# fCPU.net
KiCad netlist of a schematic drawn in EAGLE
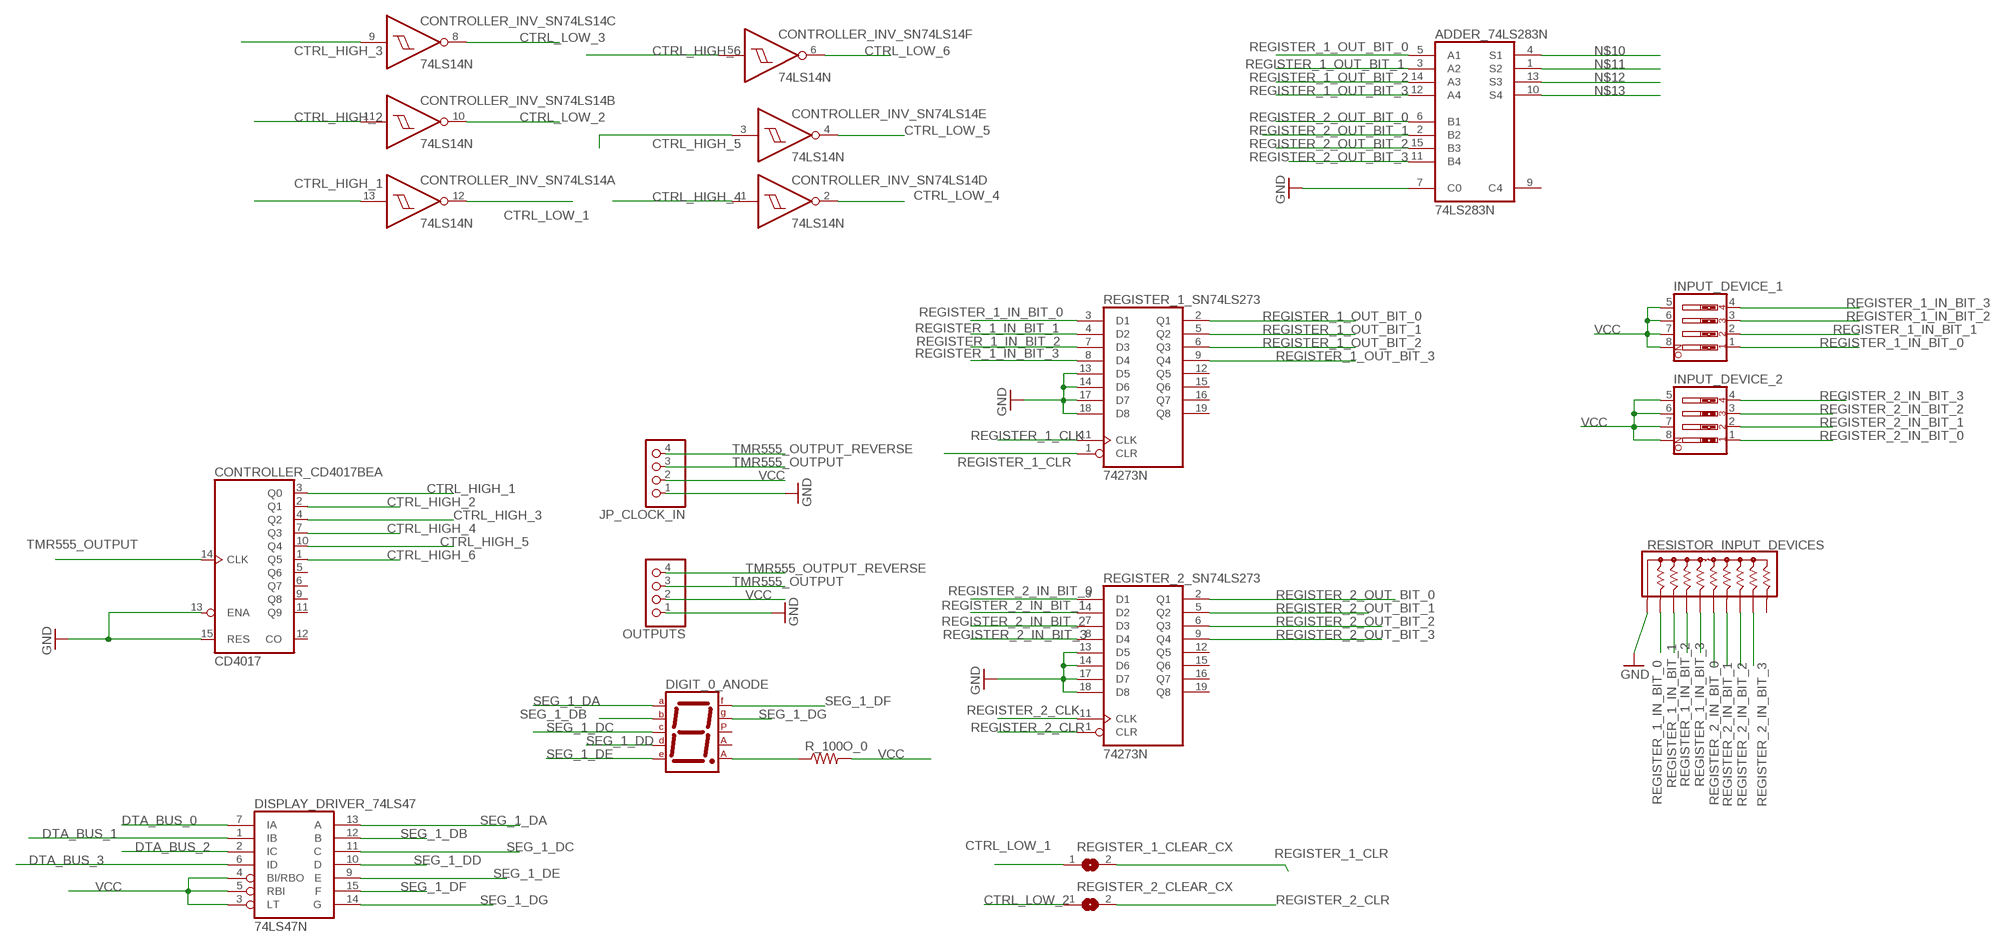
[diagram p0: schematic, sheet 1]

(export (version "E")
  (design (tool "Eeschema 10.0.6"))
  (components
    (comp (ref "ADDER_74LS283N")
      (value "74LS283N")
      (footprint "eagle-import:DIL16")
      (libsource (lib "eagle-import") (part "74283NLS"))
    )
    (comp (ref "CONTROLLER_CD4017BE")
      (value "CD4017")
      (footprint "eagle-import:DIL16")
      (libsource (lib "eagle-import") (part "CD4017"))
    )
    (comp (ref "CONTROLLER_INV_SN74LS14")
      (value "74LS14N")
      (footprint "eagle-import:DIL14")
      (libsource (lib "eagle-import") (part "7414NLS"))
    )
    (comp (ref "DIGIT_0_ANODE")
      (value "7SEG-CA")
      (footprint "eagle-import:7SEG-13")
      (libsource (lib "eagle-import") (part "7SEG-CA"))
    )
    (comp (ref "DISPLAY_DRIVER_74LS47")
      (value "74LS47N")
      (footprint "eagle-import:DIL16")
      (libsource (lib "eagle-import") (part "7447NLS"))
    )
    (comp (ref "INPUT_DEVICE_1")
      (value "SW_DIP-4")
      (footprint "eagle-import:EDG-04")
      (libsource (lib "eagle-import") (part "SW_DIP-4"))
    )
    (comp (ref "INPUT_DEVICE_2")
      (value "SW_DIP-4")
      (footprint "eagle-import:EDG-04")
      (libsource (lib "eagle-import") (part "SW_DIP-4"))
    )
    (comp (ref "JP_CLOCK_IN")
      (value "PINHD-1X4")
      (footprint "eagle-import:1X04")
      (libsource (lib "eagle-import") (part "PINHD-1X4"))
    )
    (comp (ref "OUTPUTS")
      (value "PINHD-1X4")
      (footprint "eagle-import:1X04")
      (libsource (lib "eagle-import") (part "PINHD-1X4"))
    )
    (comp (ref "REGISTER_1_CLEAR_CX")
      (value "SOLDERJUMPERREFLOW")
      (footprint "eagle-import:SOLDERJUMPER_REFLOW")
      (libsource (lib "eagle-import") (part "SOLDERJUMPERREFLOW"))
    )
    (comp (ref "REGISTER_1_SN74LS273")
      (value "74273N")
      (footprint "eagle-import:DIL20")
      (libsource (lib "eagle-import") (part "74273N"))
    )
    (comp (ref "REGISTER_2_CLEAR_CX")
      (value "SOLDERJUMPERREFLOW")
      (footprint "eagle-import:SOLDERJUMPER_REFLOW")
      (libsource (lib "eagle-import") (part "SOLDERJUMPERREFLOW"))
    )
    (comp (ref "REGISTER_2_SN74LS273")
      (value "74273N")
      (footprint "eagle-import:DIL20")
      (libsource (lib "eagle-import") (part "74273N"))
    )
    (comp (ref "RESISTOR_INPUT_DEVICES")
      (value "4610X")
      (footprint "eagle-import:SIP10")
      (libsource (lib "eagle-import") (part "4610X"))
    )
    (comp (ref "R_100O_0")
      (value "R-US_R1206")
      (footprint "eagle-import:R1206")
      (libsource (lib "eagle-import") (part "R-US_R1206"))
    )
  )
  (nets
    (net (code "1") (name "/CTRL_HIGH_1") (class "Default")
      (node (ref "CONTROLLER_CD4017BE") (pin "3") (pinfunction "Q0_3") (pintype "output"))
      (node (ref "CONTROLLER_INV_SN74LS14") (pin "13") (pinfunction "I_13") (pintype "input"))
    )
    (net (code "2") (name "/CTRL_HIGH_2") (class "Default")
      (node (ref "CONTROLLER_CD4017BE") (pin "2") (pinfunction "Q1_2") (pintype "output"))
      (node (ref "CONTROLLER_INV_SN74LS14") (pin "11") (pinfunction "I_11") (pintype "input"))
    )
    (net (code "3") (name "/CTRL_HIGH_3") (class "Default")
      (node (ref "CONTROLLER_CD4017BE") (pin "4") (pinfunction "Q2_4") (pintype "output"))
      (node (ref "CONTROLLER_INV_SN74LS14") (pin "9") (pinfunction "I_9") (pintype "input"))
    )
    (net (code "4") (name "/CTRL_HIGH_4") (class "Default")
      (node (ref "CONTROLLER_CD4017BE") (pin "7") (pinfunction "Q3_7") (pintype "output"))
      (node (ref "CONTROLLER_INV_SN74LS14") (pin "1") (pinfunction "I_1") (pintype "input"))
    )
    (net (code "5") (name "/CTRL_HIGH_5") (class "Default")
      (node (ref "CONTROLLER_CD4017BE") (pin "10") (pinfunction "Q4_10") (pintype "output"))
      (node (ref "CONTROLLER_INV_SN74LS14") (pin "3") (pinfunction "I_3") (pintype "input"))
    )
    (net (code "6") (name "/CTRL_HIGH_6") (class "Default")
      (node (ref "CONTROLLER_CD4017BE") (pin "1") (pinfunction "Q5_1") (pintype "output"))
      (node (ref "CONTROLLER_INV_SN74LS14") (pin "5") (pinfunction "I_5") (pintype "input"))
    )
    (net (code "7") (name "/CTRL_LOW_1") (class "Default")
      (node (ref "CONTROLLER_INV_SN74LS14") (pin "12") (pinfunction "O_12") (pintype "output"))
      (node (ref "REGISTER_1_CLEAR_CX") (pin "1") (pinfunction "1_1") (pintype "passive"))
    )
    (net (code "8") (name "/CTRL_LOW_2") (class "Default")
      (node (ref "CONTROLLER_INV_SN74LS14") (pin "10") (pinfunction "O_10") (pintype "output"))
      (node (ref "REGISTER_2_CLEAR_CX") (pin "1") (pinfunction "1_1") (pintype "passive"))
    )
    (net (code "9") (name "/CTRL_LOW_3") (class "Default")
      (node (ref "CONTROLLER_INV_SN74LS14") (pin "8") (pinfunction "O_8") (pintype "output"))
    )
    (net (code "10") (name "/CTRL_LOW_4") (class "Default")
      (node (ref "CONTROLLER_INV_SN74LS14") (pin "2") (pinfunction "O_2") (pintype "output"))
    )
    (net (code "11") (name "/CTRL_LOW_5") (class "Default")
      (node (ref "CONTROLLER_INV_SN74LS14") (pin "4") (pinfunction "O_4") (pintype "output"))
    )
    (net (code "12") (name "/CTRL_LOW_6") (class "Default")
      (node (ref "CONTROLLER_INV_SN74LS14") (pin "6") (pinfunction "O_6") (pintype "output"))
    )
    (net (code "13") (name "/DTA_BUS_0") (class "Default")
      (node (ref "DISPLAY_DRIVER_74LS47") (pin "7") (pinfunction "IA_7") (pintype "input"))
    )
    (net (code "14") (name "/DTA_BUS_1") (class "Default")
      (node (ref "DISPLAY_DRIVER_74LS47") (pin "1") (pinfunction "IB_1") (pintype "input"))
    )
    (net (code "15") (name "/DTA_BUS_2") (class "Default")
      (node (ref "DISPLAY_DRIVER_74LS47") (pin "2") (pinfunction "IC_2") (pintype "input"))
    )
    (net (code "16") (name "/DTA_BUS_3") (class "Default")
      (node (ref "DISPLAY_DRIVER_74LS47") (pin "6") (pinfunction "ID_6") (pintype "input"))
    )
    (net (code "17") (name "/N$10") (class "Default")
      (node (ref "ADDER_74LS283N") (pin "4") (pinfunction "S1_4") (pintype "output"))
    )
    (net (code "18") (name "/N$11") (class "Default")
      (node (ref "ADDER_74LS283N") (pin "1") (pinfunction "S2_1") (pintype "output"))
    )
    (net (code "19") (name "/N$12") (class "Default")
      (node (ref "ADDER_74LS283N") (pin "13") (pinfunction "S3_13") (pintype "output"))
    )
    (net (code "20") (name "/N$13") (class "Default")
      (node (ref "ADDER_74LS283N") (pin "10") (pinfunction "S4_10") (pintype "output"))
    )
    (net (code "21") (name "/REGISTER_1_CLK") (class "Default")
      (node (ref "REGISTER_1_SN74LS273") (pin "11") (pinfunction "CLK_11") (pintype "input"))
    )
    (net (code "22") (name "/REGISTER_1_CLR") (class "Default")
      (node (ref "REGISTER_1_CLEAR_CX") (pin "2") (pinfunction "2_2") (pintype "passive"))
      (node (ref "REGISTER_1_SN74LS273") (pin "1") (pinfunction "CLR_1") (pintype "input"))
    )
    (net (code "23") (name "/REGISTER_1_IN_BIT_0") (class "Default")
      (node (ref "INPUT_DEVICE_1") (pin "1") (pinfunction "1_1") (pintype "passive"))
      (node (ref "REGISTER_1_SN74LS273") (pin "3") (pinfunction "D1_3") (pintype "input"))
      (node (ref "RESISTOR_INPUT_DEVICES") (pin "2") (pinfunction "2_2") (pintype "passive"))
    )
    (net (code "24") (name "/REGISTER_1_IN_BIT_1") (class "Default")
      (node (ref "INPUT_DEVICE_1") (pin "2") (pinfunction "2_2") (pintype "passive"))
      (node (ref "REGISTER_1_SN74LS273") (pin "4") (pinfunction "D2_4") (pintype "input"))
      (node (ref "RESISTOR_INPUT_DEVICES") (pin "3") (pinfunction "3_3") (pintype "passive"))
    )
    (net (code "25") (name "/REGISTER_1_IN_BIT_2") (class "Default")
      (node (ref "INPUT_DEVICE_1") (pin "3") (pinfunction "3_3") (pintype "passive"))
      (node (ref "REGISTER_1_SN74LS273") (pin "7") (pinfunction "D3_7") (pintype "input"))
      (node (ref "RESISTOR_INPUT_DEVICES") (pin "4") (pinfunction "4_4") (pintype "passive"))
    )
    (net (code "26") (name "/REGISTER_1_IN_BIT_3") (class "Default")
      (node (ref "INPUT_DEVICE_1") (pin "4") (pinfunction "4_4") (pintype "passive"))
      (node (ref "REGISTER_1_SN74LS273") (pin "8") (pinfunction "D4_8") (pintype "input"))
      (node (ref "RESISTOR_INPUT_DEVICES") (pin "5") (pinfunction "5_5") (pintype "passive"))
    )
    (net (code "27") (name "/REGISTER_1_OUT_BIT_0") (class "Default")
      (node (ref "ADDER_74LS283N") (pin "5") (pinfunction "A1_5") (pintype "input"))
      (node (ref "REGISTER_1_SN74LS273") (pin "2") (pinfunction "Q1_2") (pintype "output"))
    )
    (net (code "28") (name "/REGISTER_1_OUT_BIT_1") (class "Default")
      (node (ref "ADDER_74LS283N") (pin "3") (pinfunction "A2_3") (pintype "input"))
      (node (ref "REGISTER_1_SN74LS273") (pin "5") (pinfunction "Q2_5") (pintype "output"))
    )
    (net (code "29") (name "/REGISTER_1_OUT_BIT_2") (class "Default")
      (node (ref "ADDER_74LS283N") (pin "14") (pinfunction "A3_14") (pintype "input"))
      (node (ref "REGISTER_1_SN74LS273") (pin "6") (pinfunction "Q3_6") (pintype "output"))
    )
    (net (code "30") (name "/REGISTER_1_OUT_BIT_3") (class "Default")
      (node (ref "ADDER_74LS283N") (pin "12") (pinfunction "A4_12") (pintype "input"))
      (node (ref "REGISTER_1_SN74LS273") (pin "9") (pinfunction "Q4_9") (pintype "output"))
    )
    (net (code "31") (name "/REGISTER_2_CLK") (class "Default")
      (node (ref "REGISTER_2_SN74LS273") (pin "11") (pinfunction "CLK_11") (pintype "input"))
    )
    (net (code "32") (name "/REGISTER_2_CLR") (class "Default")
      (node (ref "REGISTER_2_CLEAR_CX") (pin "2") (pinfunction "2_2") (pintype "passive"))
      (node (ref "REGISTER_2_SN74LS273") (pin "1") (pinfunction "CLR_1") (pintype "input"))
    )
    (net (code "33") (name "/REGISTER_2_IN_BIT_0") (class "Default")
      (node (ref "INPUT_DEVICE_2") (pin "1") (pinfunction "1_1") (pintype "passive"))
      (node (ref "REGISTER_2_SN74LS273") (pin "3") (pinfunction "D1_3") (pintype "input"))
      (node (ref "RESISTOR_INPUT_DEVICES") (pin "6") (pinfunction "6_6") (pintype "passive"))
    )
    (net (code "34") (name "/REGISTER_2_IN_BIT_1") (class "Default")
      (node (ref "INPUT_DEVICE_2") (pin "2") (pinfunction "2_2") (pintype "passive"))
      (node (ref "REGISTER_2_SN74LS273") (pin "4") (pinfunction "D2_4") (pintype "input"))
      (node (ref "RESISTOR_INPUT_DEVICES") (pin "7") (pinfunction "7_7") (pintype "passive"))
    )
    (net (code "35") (name "/REGISTER_2_IN_BIT_2") (class "Default")
      (node (ref "INPUT_DEVICE_2") (pin "3") (pinfunction "3_3") (pintype "passive"))
      (node (ref "REGISTER_2_SN74LS273") (pin "7") (pinfunction "D3_7") (pintype "input"))
      (node (ref "RESISTOR_INPUT_DEVICES") (pin "8") (pinfunction "8_8") (pintype "passive"))
    )
    (net (code "36") (name "/REGISTER_2_IN_BIT_3") (class "Default")
      (node (ref "INPUT_DEVICE_2") (pin "4") (pinfunction "4_4") (pintype "passive"))
      (node (ref "REGISTER_2_SN74LS273") (pin "8") (pinfunction "D4_8") (pintype "input"))
      (node (ref "RESISTOR_INPUT_DEVICES") (pin "9") (pinfunction "9_9") (pintype "passive"))
    )
    (net (code "37") (name "/REGISTER_2_OUT_BIT_0") (class "Default")
      (node (ref "ADDER_74LS283N") (pin "6") (pinfunction "B1_6") (pintype "input"))
      (node (ref "REGISTER_2_SN74LS273") (pin "2") (pinfunction "Q1_2") (pintype "output"))
    )
    (net (code "38") (name "/REGISTER_2_OUT_BIT_1") (class "Default")
      (node (ref "ADDER_74LS283N") (pin "2") (pinfunction "B2_2") (pintype "input"))
      (node (ref "REGISTER_2_SN74LS273") (pin "5") (pinfunction "Q2_5") (pintype "output"))
    )
    (net (code "39") (name "/REGISTER_2_OUT_BIT_2") (class "Default")
      (node (ref "ADDER_74LS283N") (pin "15") (pinfunction "B3_15") (pintype "input"))
      (node (ref "REGISTER_2_SN74LS273") (pin "6") (pinfunction "Q3_6") (pintype "output"))
    )
    (net (code "40") (name "/REGISTER_2_OUT_BIT_3") (class "Default")
      (node (ref "ADDER_74LS283N") (pin "11") (pinfunction "B4_11") (pintype "input"))
      (node (ref "REGISTER_2_SN74LS273") (pin "9") (pinfunction "Q4_9") (pintype "output"))
    )
    (net (code "41") (name "/SEG_1_DA") (class "Default")
      (node (ref "DIGIT_0_ANODE") (pin "7") (pinfunction "A_7") (pintype "passive"))
      (node (ref "DISPLAY_DRIVER_74LS47") (pin "13") (pinfunction "A_13") (pintype "output"))
    )
    (net (code "42") (name "/SEG_1_DB") (class "Default")
      (node (ref "DIGIT_0_ANODE") (pin "6") (pinfunction "B_6") (pintype "passive"))
      (node (ref "DISPLAY_DRIVER_74LS47") (pin "12") (pinfunction "B_12") (pintype "output"))
    )
    (net (code "43") (name "/SEG_1_DC") (class "Default")
      (node (ref "DIGIT_0_ANODE") (pin "4") (pinfunction "C_4") (pintype "passive"))
      (node (ref "DISPLAY_DRIVER_74LS47") (pin "11") (pinfunction "C_11") (pintype "output"))
    )
    (net (code "44") (name "/SEG_1_DD") (class "Default")
      (node (ref "DIGIT_0_ANODE") (pin "2") (pinfunction "D_2") (pintype "passive"))
      (node (ref "DISPLAY_DRIVER_74LS47") (pin "10") (pinfunction "D_10") (pintype "output"))
    )
    (net (code "45") (name "/SEG_1_DE") (class "Default")
      (node (ref "DIGIT_0_ANODE") (pin "1") (pinfunction "E_1") (pintype "passive"))
      (node (ref "DISPLAY_DRIVER_74LS47") (pin "9") (pinfunction "E_9") (pintype "output"))
    )
    (net (code "46") (name "/SEG_1_DF") (class "Default")
      (node (ref "DIGIT_0_ANODE") (pin "9") (pinfunction "F_9") (pintype "passive"))
      (node (ref "DISPLAY_DRIVER_74LS47") (pin "15") (pinfunction "F_15") (pintype "output"))
    )
    (net (code "47") (name "/SEG_1_DG") (class "Default")
      (node (ref "DIGIT_0_ANODE") (pin "10") (pinfunction "G_10") (pintype "passive"))
      (node (ref "DISPLAY_DRIVER_74LS47") (pin "14") (pinfunction "G_14") (pintype "output"))
    )
    (net (code "48") (name "/TMR555_OUTPUT") (class "Default")
      (node (ref "CONTROLLER_CD4017BE") (pin "14") (pinfunction "CLK_14") (pintype "input"))
      (node (ref "JP_CLOCK_IN") (pin "3") (pinfunction "3_3") (pintype "passive"))
      (node (ref "OUTPUTS") (pin "3") (pinfunction "3_3") (pintype "passive"))
    )
    (net (code "49") (name "/TMR555_OUTPUT_REVERSE") (class "Default")
      (node (ref "JP_CLOCK_IN") (pin "4") (pinfunction "4_4") (pintype "passive"))
      (node (ref "OUTPUTS") (pin "4") (pinfunction "4_4") (pintype "passive"))
    )
    (net (code "50") (name "/VCC") (class "Default")
      (node (ref "DISPLAY_DRIVER_74LS47") (pin "3") (pinfunction "LT_3") (pintype "input"))
      (node (ref "DISPLAY_DRIVER_74LS47") (pin "4") (pinfunction "BI/RBO_4") (pintype "input"))
      (node (ref "DISPLAY_DRIVER_74LS47") (pin "5") (pinfunction "RBI_5") (pintype "input"))
      (node (ref "INPUT_DEVICE_1") (pin "5") (pinfunction "5_5") (pintype "passive"))
      (node (ref "INPUT_DEVICE_1") (pin "6") (pinfunction "6_6") (pintype "passive"))
      (node (ref "INPUT_DEVICE_1") (pin "7") (pinfunction "7_7") (pintype "passive"))
      (node (ref "INPUT_DEVICE_1") (pin "8") (pinfunction "8_8") (pintype "passive"))
      (node (ref "INPUT_DEVICE_2") (pin "5") (pinfunction "5_5") (pintype "passive"))
      (node (ref "INPUT_DEVICE_2") (pin "6") (pinfunction "6_6") (pintype "passive"))
      (node (ref "INPUT_DEVICE_2") (pin "7") (pinfunction "7_7") (pintype "passive"))
      (node (ref "INPUT_DEVICE_2") (pin "8") (pinfunction "8_8") (pintype "passive"))
      (node (ref "JP_CLOCK_IN") (pin "2") (pinfunction "2_2") (pintype "passive"))
      (node (ref "OUTPUTS") (pin "2") (pinfunction "2_2") (pintype "passive"))
      (node (ref "R_100O_0") (pin "2") (pinfunction "2_2") (pintype "passive"))
    )
    (net (code "51") (name "GND") (class "Default")
      (node (ref "ADDER_74LS283N") (pin "7") (pinfunction "C0_7") (pintype "input"))
      (node (ref "CONTROLLER_CD4017BE") (pin "13") (pinfunction "ENA_13") (pintype "input"))
      (node (ref "CONTROLLER_CD4017BE") (pin "15") (pinfunction "RES_15") (pintype "input"))
      (node (ref "JP_CLOCK_IN") (pin "1") (pinfunction "1_1") (pintype "passive"))
      (node (ref "OUTPUTS") (pin "1") (pinfunction "1_1") (pintype "passive"))
      (node (ref "REGISTER_1_SN74LS273") (pin "13") (pinfunction "D5_13") (pintype "input"))
      (node (ref "REGISTER_1_SN74LS273") (pin "14") (pinfunction "D6_14") (pintype "input"))
      (node (ref "REGISTER_1_SN74LS273") (pin "17") (pinfunction "D7_17") (pintype "input"))
      (node (ref "REGISTER_1_SN74LS273") (pin "18") (pinfunction "D8_18") (pintype "input"))
      (node (ref "REGISTER_2_SN74LS273") (pin "13") (pinfunction "D5_13") (pintype "input"))
      (node (ref "REGISTER_2_SN74LS273") (pin "14") (pinfunction "D6_14") (pintype "input"))
      (node (ref "REGISTER_2_SN74LS273") (pin "17") (pinfunction "D7_17") (pintype "input"))
      (node (ref "REGISTER_2_SN74LS273") (pin "18") (pinfunction "D8_18") (pintype "input"))
      (node (ref "RESISTOR_INPUT_DEVICES") (pin "1") (pinfunction "1_1") (pintype "passive"))
    )
    (net (code "52") (name "Net-(DIGIT_0_ANODE-CA2)") (class "Default")
      (node (ref "DIGIT_0_ANODE") (pin "8") (pinfunction "CA2_8") (pintype "passive"))
      (node (ref "R_100O_0") (pin "1") (pinfunction "1_1") (pintype "passive"))
    )
    (net (code "53") (name "unconnected-(ADDER_74LS283NA-C4-Pad9)") (class "Default")
      (node (ref "ADDER_74LS283N") (pin "9") (pinfunction "C4_9") (pintype "output"))
    )
    (net (code "54") (name "unconnected-(CONTROLLER_CD4017BEA-CO-Pad12)") (class "Default")
      (node (ref "CONTROLLER_CD4017BE") (pin "12") (pinfunction "CO_12") (pintype "output"))
    )
    (net (code "55") (name "unconnected-(CONTROLLER_CD4017BEA-Q6-Pad5)") (class "Default")
      (node (ref "CONTROLLER_CD4017BE") (pin "5") (pinfunction "Q6_5") (pintype "output"))
    )
    (net (code "56") (name "unconnected-(CONTROLLER_CD4017BEA-Q7-Pad6)") (class "Default")
      (node (ref "CONTROLLER_CD4017BE") (pin "6") (pinfunction "Q7_6") (pintype "output"))
    )
    (net (code "57") (name "unconnected-(CONTROLLER_CD4017BEA-Q8-Pad9)") (class "Default")
      (node (ref "CONTROLLER_CD4017BE") (pin "9") (pinfunction "Q8_9") (pintype "output"))
    )
    (net (code "58") (name "unconnected-(CONTROLLER_CD4017BEA-Q9-Pad11)") (class "Default")
      (node (ref "CONTROLLER_CD4017BE") (pin "11") (pinfunction "Q9_11") (pintype "output"))
    )
    (net (code "59") (name "unconnected-(DIGIT_0_ANODE-CA1-Pad3)") (class "Default")
      (node (ref "DIGIT_0_ANODE") (pin "3") (pinfunction "CA1_3") (pintype "passive"))
    )
    (net (code "60") (name "unconnected-(DIGIT_0_ANODE-DP-Pad5)") (class "Default")
      (node (ref "DIGIT_0_ANODE") (pin "5") (pinfunction "DP_5") (pintype "passive"))
    )
    (net (code "61") (name "unconnected-(REGISTER_1_SN74LS273A-Q5-Pad12)") (class "Default")
      (node (ref "REGISTER_1_SN74LS273") (pin "12") (pinfunction "Q5_12") (pintype "output"))
    )
    (net (code "62") (name "unconnected-(REGISTER_1_SN74LS273A-Q6-Pad15)") (class "Default")
      (node (ref "REGISTER_1_SN74LS273") (pin "15") (pinfunction "Q6_15") (pintype "output"))
    )
    (net (code "63") (name "unconnected-(REGISTER_1_SN74LS273A-Q7-Pad16)") (class "Default")
      (node (ref "REGISTER_1_SN74LS273") (pin "16") (pinfunction "Q7_16") (pintype "output"))
    )
    (net (code "64") (name "unconnected-(REGISTER_1_SN74LS273A-Q8-Pad19)") (class "Default")
      (node (ref "REGISTER_1_SN74LS273") (pin "19") (pinfunction "Q8_19") (pintype "output"))
    )
    (net (code "65") (name "unconnected-(REGISTER_2_SN74LS273A-Q5-Pad12)") (class "Default")
      (node (ref "REGISTER_2_SN74LS273") (pin "12") (pinfunction "Q5_12") (pintype "output"))
    )
    (net (code "66") (name "unconnected-(REGISTER_2_SN74LS273A-Q6-Pad15)") (class "Default")
      (node (ref "REGISTER_2_SN74LS273") (pin "15") (pinfunction "Q6_15") (pintype "output"))
    )
    (net (code "67") (name "unconnected-(REGISTER_2_SN74LS273A-Q7-Pad16)") (class "Default")
      (node (ref "REGISTER_2_SN74LS273") (pin "16") (pinfunction "Q7_16") (pintype "output"))
    )
    (net (code "68") (name "unconnected-(REGISTER_2_SN74LS273A-Q8-Pad19)") (class "Default")
      (node (ref "REGISTER_2_SN74LS273") (pin "19") (pinfunction "Q8_19") (pintype "output"))
    )
    (net (code "69") (name "unconnected-(RESISTOR_INPUT_DEVICES-Pad10)") (class "Default")
      (node (ref "RESISTOR_INPUT_DEVICES") (pin "10") (pinfunction "10_10") (pintype "passive"))
    )
  )
)
